# WingFly-Shield_v10.net
KiCad netlist of a schematic drawn in EAGLE
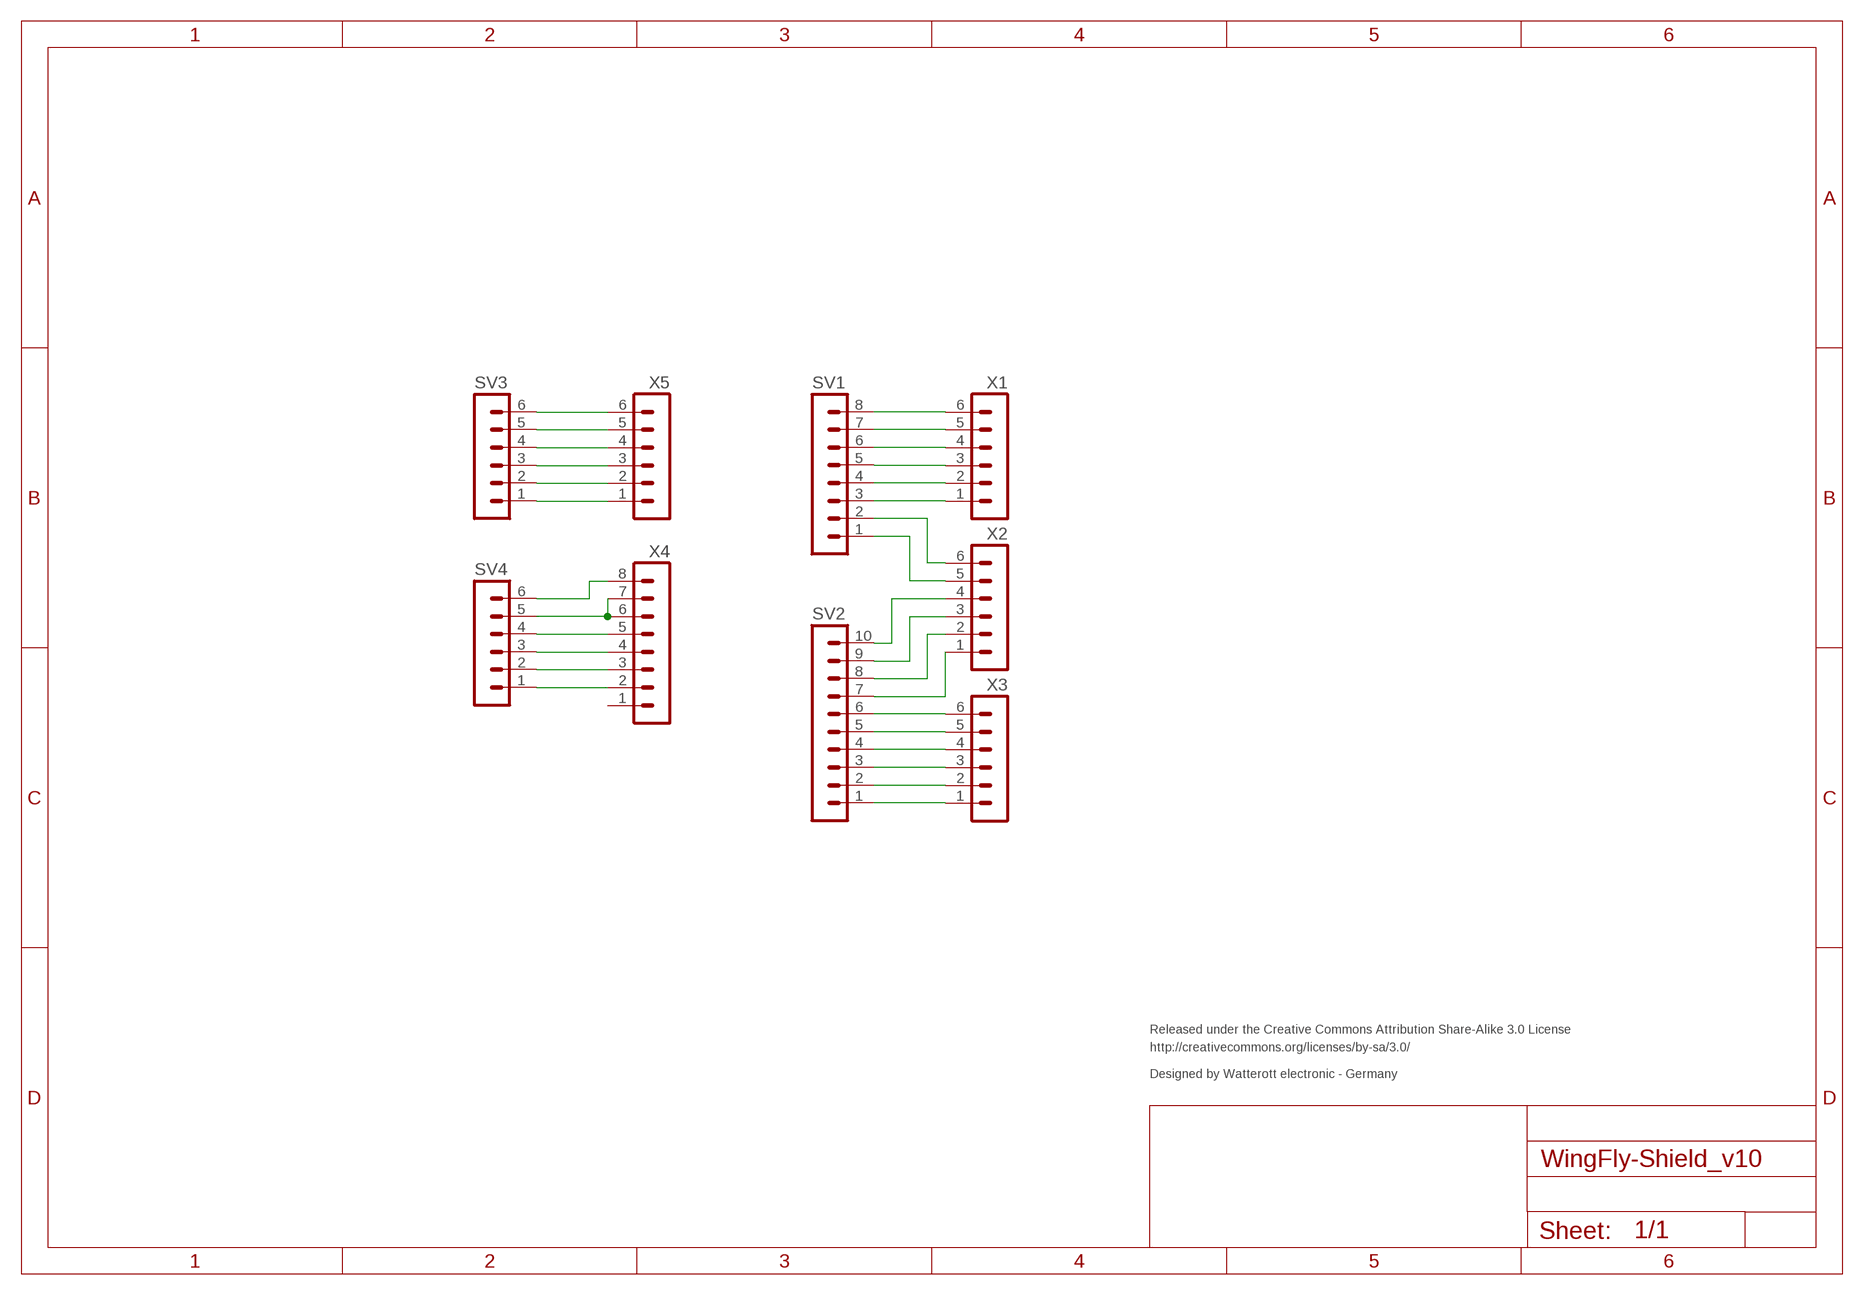
[diagram p0: schematic, sheet 1]

(export (version "E")
  (design (tool "Eeschema 10.0.6"))
  (components
    (comp (ref "SV1")
      (value "MA08-1")
      (footprint "eagle-import:MA08-1")
      (libsource (lib "eagle-import") (part "MA08-1"))
    )
    (comp (ref "SV2")
      (value "MA10-1")
      (footprint "eagle-import:MA10-1")
      (libsource (lib "eagle-import") (part "MA10-1"))
    )
    (comp (ref "SV3")
      (value "MA06-1")
      (footprint "eagle-import:MA06-1")
      (libsource (lib "eagle-import") (part "MA06-1"))
    )
    (comp (ref "SV4")
      (value "MA06-1")
      (footprint "eagle-import:MA06-1")
      (libsource (lib "eagle-import") (part "MA06-1"))
    )
    (comp (ref "X1")
      (value "MA06-1")
      (footprint "eagle-import:MA06-1")
      (libsource (lib "eagle-import") (part "MA06-1"))
    )
    (comp (ref "X2")
      (value "MA06-1")
      (footprint "eagle-import:MA06-1")
      (libsource (lib "eagle-import") (part "MA06-1"))
    )
    (comp (ref "X3")
      (value "MA06-1")
      (footprint "eagle-import:MA06-1")
      (libsource (lib "eagle-import") (part "MA06-1"))
    )
    (comp (ref "X4")
      (value "MA08-1")
      (footprint "eagle-import:MA08-1")
      (libsource (lib "eagle-import") (part "MA08-1"))
    )
    (comp (ref "X5")
      (value "MA06-1")
      (footprint "eagle-import:MA06-1")
      (libsource (lib "eagle-import") (part "MA06-1"))
    )
  )
  (nets
    (net (code "1") (name "Net-(SV1-Pad1)") (class "Default")
      (node (ref "SV1") (pin "1") (pinfunction "1_1") (pintype "passive"))
      (node (ref "X2") (pin "5") (pinfunction "5_5") (pintype "passive"))
    )
    (net (code "2") (name "Net-(SV1-Pad2)") (class "Default")
      (node (ref "SV1") (pin "2") (pinfunction "2_2") (pintype "passive"))
      (node (ref "X2") (pin "6") (pinfunction "6_6") (pintype "passive"))
    )
    (net (code "3") (name "Net-(SV1-Pad3)") (class "Default")
      (node (ref "SV1") (pin "3") (pinfunction "3_3") (pintype "passive"))
      (node (ref "X1") (pin "1") (pinfunction "1_1") (pintype "passive"))
    )
    (net (code "4") (name "Net-(SV1-Pad4)") (class "Default")
      (node (ref "SV1") (pin "4") (pinfunction "4_4") (pintype "passive"))
      (node (ref "X1") (pin "2") (pinfunction "2_2") (pintype "passive"))
    )
    (net (code "5") (name "Net-(SV1-Pad5)") (class "Default")
      (node (ref "SV1") (pin "5") (pinfunction "5_5") (pintype "passive"))
      (node (ref "X1") (pin "3") (pinfunction "3_3") (pintype "passive"))
    )
    (net (code "6") (name "Net-(SV1-Pad6)") (class "Default")
      (node (ref "SV1") (pin "6") (pinfunction "6_6") (pintype "passive"))
      (node (ref "X1") (pin "4") (pinfunction "4_4") (pintype "passive"))
    )
    (net (code "7") (name "Net-(SV1-Pad7)") (class "Default")
      (node (ref "SV1") (pin "7") (pinfunction "7_7") (pintype "passive"))
      (node (ref "X1") (pin "5") (pinfunction "5_5") (pintype "passive"))
    )
    (net (code "8") (name "Net-(SV1-Pad8)") (class "Default")
      (node (ref "SV1") (pin "8") (pinfunction "8_8") (pintype "passive"))
      (node (ref "X1") (pin "6") (pinfunction "6_6") (pintype "passive"))
    )
    (net (code "9") (name "Net-(SV2-Pad1)") (class "Default")
      (node (ref "SV2") (pin "1") (pinfunction "1_1") (pintype "passive"))
      (node (ref "X3") (pin "1") (pinfunction "1_1") (pintype "passive"))
    )
    (net (code "10") (name "Net-(SV2-Pad2)") (class "Default")
      (node (ref "SV2") (pin "2") (pinfunction "2_2") (pintype "passive"))
      (node (ref "X3") (pin "2") (pinfunction "2_2") (pintype "passive"))
    )
    (net (code "11") (name "Net-(SV2-Pad3)") (class "Default")
      (node (ref "SV2") (pin "3") (pinfunction "3_3") (pintype "passive"))
      (node (ref "X3") (pin "3") (pinfunction "3_3") (pintype "passive"))
    )
    (net (code "12") (name "Net-(SV2-Pad4)") (class "Default")
      (node (ref "SV2") (pin "4") (pinfunction "4_4") (pintype "passive"))
      (node (ref "X3") (pin "4") (pinfunction "4_4") (pintype "passive"))
    )
    (net (code "13") (name "Net-(SV2-Pad5)") (class "Default")
      (node (ref "SV2") (pin "5") (pinfunction "5_5") (pintype "passive"))
      (node (ref "X3") (pin "5") (pinfunction "5_5") (pintype "passive"))
    )
    (net (code "14") (name "Net-(SV2-Pad6)") (class "Default")
      (node (ref "SV2") (pin "6") (pinfunction "6_6") (pintype "passive"))
      (node (ref "X3") (pin "6") (pinfunction "6_6") (pintype "passive"))
    )
    (net (code "15") (name "Net-(SV2-Pad7)") (class "Default")
      (node (ref "SV2") (pin "7") (pinfunction "7_7") (pintype "passive"))
      (node (ref "X2") (pin "1") (pinfunction "1_1") (pintype "passive"))
    )
    (net (code "16") (name "Net-(SV2-Pad8)") (class "Default")
      (node (ref "SV2") (pin "8") (pinfunction "8_8") (pintype "passive"))
      (node (ref "X2") (pin "2") (pinfunction "2_2") (pintype "passive"))
    )
    (net (code "17") (name "Net-(SV2-Pad9)") (class "Default")
      (node (ref "SV2") (pin "9") (pinfunction "9_9") (pintype "passive"))
      (node (ref "X2") (pin "3") (pinfunction "3_3") (pintype "passive"))
    )
    (net (code "18") (name "Net-(SV2-Pad10)") (class "Default")
      (node (ref "SV2") (pin "10") (pinfunction "10_10") (pintype "passive"))
      (node (ref "X2") (pin "4") (pinfunction "4_4") (pintype "passive"))
    )
    (net (code "19") (name "Net-(SV3-Pad1)") (class "Default")
      (node (ref "SV3") (pin "1") (pinfunction "1_1") (pintype "passive"))
      (node (ref "X5") (pin "1") (pinfunction "1_1") (pintype "passive"))
    )
    (net (code "20") (name "Net-(SV3-Pad2)") (class "Default")
      (node (ref "SV3") (pin "2") (pinfunction "2_2") (pintype "passive"))
      (node (ref "X5") (pin "2") (pinfunction "2_2") (pintype "passive"))
    )
    (net (code "21") (name "Net-(SV3-Pad3)") (class "Default")
      (node (ref "SV3") (pin "3") (pinfunction "3_3") (pintype "passive"))
      (node (ref "X5") (pin "3") (pinfunction "3_3") (pintype "passive"))
    )
    (net (code "22") (name "Net-(SV3-Pad4)") (class "Default")
      (node (ref "SV3") (pin "4") (pinfunction "4_4") (pintype "passive"))
      (node (ref "X5") (pin "4") (pinfunction "4_4") (pintype "passive"))
    )
    (net (code "23") (name "Net-(SV3-Pad5)") (class "Default")
      (node (ref "SV3") (pin "5") (pinfunction "5_5") (pintype "passive"))
      (node (ref "X5") (pin "5") (pinfunction "5_5") (pintype "passive"))
    )
    (net (code "24") (name "Net-(SV3-Pad6)") (class "Default")
      (node (ref "SV3") (pin "6") (pinfunction "6_6") (pintype "passive"))
      (node (ref "X5") (pin "6") (pinfunction "6_6") (pintype "passive"))
    )
    (net (code "25") (name "Net-(SV4-Pad1)") (class "Default")
      (node (ref "SV4") (pin "1") (pinfunction "1_1") (pintype "passive"))
      (node (ref "X4") (pin "2") (pinfunction "2_2") (pintype "passive"))
    )
    (net (code "26") (name "Net-(SV4-Pad2)") (class "Default")
      (node (ref "SV4") (pin "2") (pinfunction "2_2") (pintype "passive"))
      (node (ref "X4") (pin "3") (pinfunction "3_3") (pintype "passive"))
    )
    (net (code "27") (name "Net-(SV4-Pad3)") (class "Default")
      (node (ref "SV4") (pin "3") (pinfunction "3_3") (pintype "passive"))
      (node (ref "X4") (pin "4") (pinfunction "4_4") (pintype "passive"))
    )
    (net (code "28") (name "Net-(SV4-Pad4)") (class "Default")
      (node (ref "SV4") (pin "4") (pinfunction "4_4") (pintype "passive"))
      (node (ref "X4") (pin "5") (pinfunction "5_5") (pintype "passive"))
    )
    (net (code "29") (name "Net-(SV4-Pad5)") (class "Default")
      (node (ref "SV4") (pin "5") (pinfunction "5_5") (pintype "passive"))
      (node (ref "X4") (pin "6") (pinfunction "6_6") (pintype "passive"))
      (node (ref "X4") (pin "7") (pinfunction "7_7") (pintype "passive"))
    )
    (net (code "30") (name "Net-(SV4-Pad6)") (class "Default")
      (node (ref "SV4") (pin "6") (pinfunction "6_6") (pintype "passive"))
      (node (ref "X4") (pin "8") (pinfunction "8_8") (pintype "passive"))
    )
    (net (code "31") (name "unconnected-(X4-Pad1)") (class "Default")
      (node (ref "X4") (pin "1") (pinfunction "1_1") (pintype "passive"))
    )
  )
)
